# Detection.net
KiCad netlist of a schematic drawn in Altium Designer
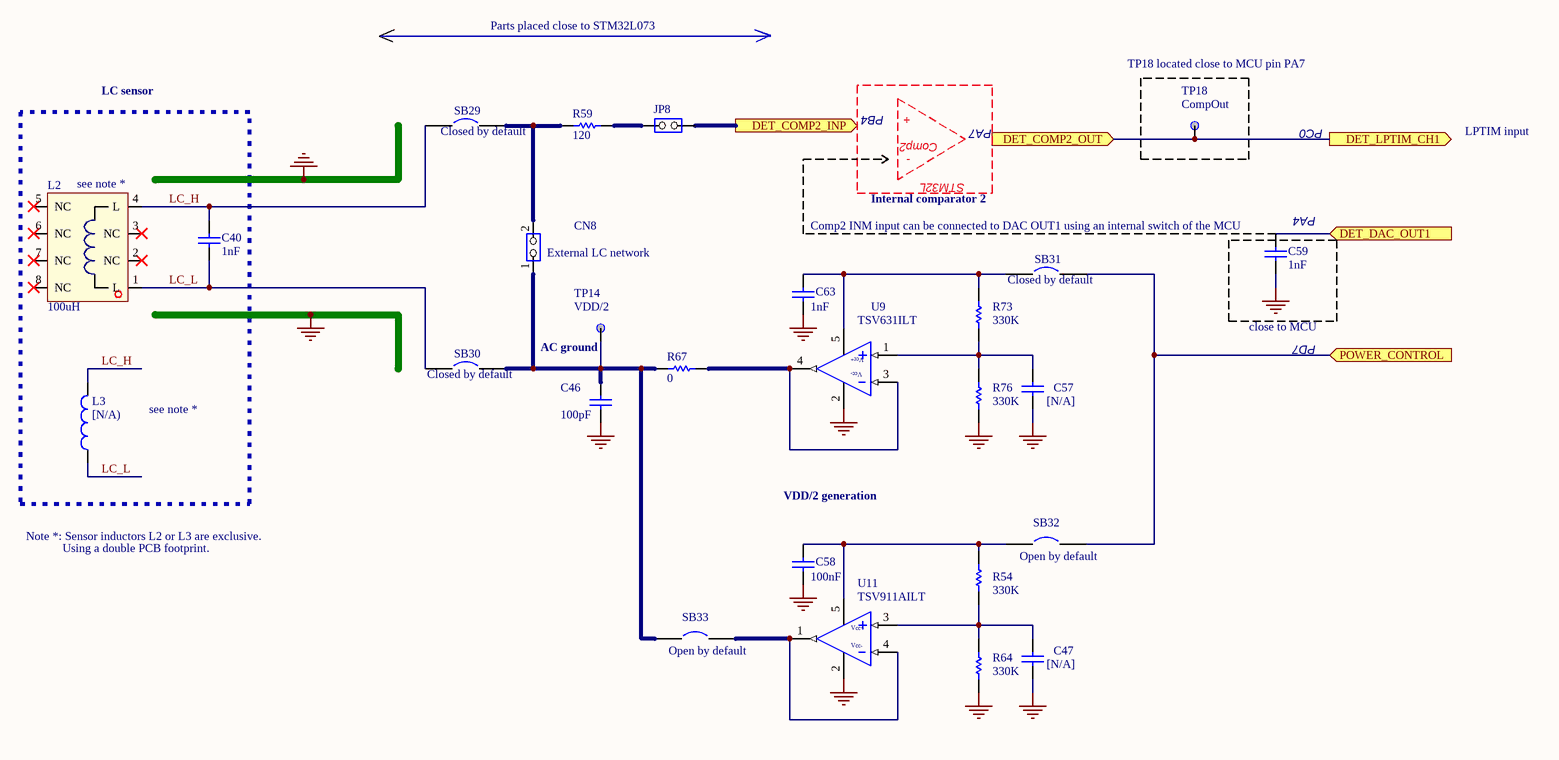
[diagram p0: Detection.SchDoc]

(export (version "E")
  (design (tool "Eeschema 10.0.6"))
  (components
    (comp (ref "C40")
      (value "1nF")
      (footprint "0603C")
      (description "Capacitor")
      (libsource (lib "MCD_TOOLS") (part "Capacitor_ST"))
    )
    (comp (ref "C46")
      (value "100pF")
      (footprint "0402C")
      (description "Capacitor")
      (libsource (lib "MCD_TOOLS") (part "Capacitor_ST"))
    )
    (comp (ref "C47")
      (value "[N/A]")
      (footprint "0603C")
      (description "Capacitor")
      (libsource (lib "MCD_TOOLS") (part "Capacitor_ST"))
    )
    (comp (ref "C57")
      (value "[N/A]")
      (footprint "0603C")
      (description "Capacitor")
      (libsource (lib "MCD_TOOLS") (part "Capacitor_ST"))
    )
    (comp (ref "C58")
      (value "100nF")
      (footprint "0402C")
      (description "Capacitor")
      (libsource (lib "MCD_TOOLS") (part "Capacitor_ST"))
    )
    (comp (ref "C59")
      (value "1nF")
      (footprint "0603C")
      (description "Capacitor")
      (libsource (lib "MCD_TOOLS") (part "Capacitor_ST"))
    )
    (comp (ref "C63")
      (value "1nF")
      (footprint "0402C")
      (description "Capacitor")
      (libsource (lib "MCD_TOOLS") (part "Capacitor_ST"))
    )
    (comp (ref "CN8")
      (value "Header 2X1")
      (footprint "SIP2")
      (fields (field (name "SILKSCREEN") "External LC network"))
      (libsource (lib "") (part "JP2_1"))
    )
    (comp (ref "JP8") (value "~") (footprint "SIP2") (libsource (lib "*") (part "JP2")))
    (comp (ref "L2")
      (value "100uH")
      (footprint "ER95")
      (description "Wurth E core inductor 750315110")
      (libsource (lib "Almos") (part "Wurth_ER9.5"))
    )
    (comp (ref "L3")
      (value "[N/A)")
      (footprint "LSM2_4R4X3R2_H3")
      (description "Cyntec/Delta  Inductor SIE4734-101")
      (fields (field (name "PUBLISHER") "Altium Limited"))
      (libsource (lib "Miscellaneous Devices") (part "Inductor"))
    )
    (comp (ref "R54")
      (value "330K")
      (footprint "0402R")
      (description "Resistor")
      (fields (field (name "PUBLISHER") "Altium Limited"))
      (libsource (lib "Miscellaneous Devices") (part "Res1"))
    )
    (comp (ref "R59")
      (value "120")
      (footprint "0603R")
      (description "Resistor")
      (fields (field (name "PUBLISHER") "Altium Limited"))
      (libsource (lib "Miscellaneous Devices") (part "Res1"))
    )
    (comp (ref "R64")
      (value "330K")
      (footprint "0402R")
      (description "Resistor")
      (fields (field (name "PUBLISHER") "Altium Limited"))
      (libsource (lib "Miscellaneous Devices") (part "Res1"))
    )
    (comp (ref "R67")
      (value "0")
      (footprint "0603R")
      (description "Resistor")
      (fields (field (name "PUBLISHER") "Altium Limited"))
      (libsource (lib "Miscellaneous Devices") (part "Res1"))
    )
    (comp (ref "R73")
      (value "330K")
      (footprint "0402R")
      (description "Resistor")
      (fields (field (name "PUBLISHER") "Altium Limited"))
      (libsource (lib "Miscellaneous Devices") (part "Res1"))
    )
    (comp (ref "R76")
      (value "330K")
      (footprint "0402R")
      (description "Resistor")
      (fields (field (name "PUBLISHER") "Altium Limited"))
      (libsource (lib "Miscellaneous Devices") (part "Res1"))
    )
    (comp (ref "SB29")
      (value "Closed by default")
      (footprint "SB_0603")
      (description "Circuit Breaker")
      (fields (field (name "PUBLISHER") "Altium Limited"))
      (libsource (lib "Miscellaneous Devices") (part "Circuit Breaker"))
    )
    (comp (ref "SB30")
      (value "Closed by default")
      (footprint "SB_0603")
      (description "Circuit Breaker")
      (fields (field (name "PUBLISHER") "Altium Limited"))
      (libsource (lib "Miscellaneous Devices") (part "Circuit Breaker"))
    )
    (comp (ref "SB31")
      (value "Closed by default")
      (footprint "SB_0603")
      (description "Circuit Breaker")
      (fields (field (name "PUBLISHER") "Altium Limited"))
      (libsource (lib "Miscellaneous Devices") (part "Circuit Breaker"))
    )
    (comp (ref "SB32")
      (value "Open by default")
      (footprint "SB_0603")
      (description "Circuit Breaker")
      (fields (field (name "PUBLISHER") "Altium Limited"))
      (libsource (lib "Miscellaneous Devices") (part "Circuit Breaker"))
    )
    (comp (ref "SB33")
      (value "Open by default")
      (footprint "SB_0603")
      (description "Circuit Breaker")
      (fields (field (name "PUBLISHER") "Altium Limited"))
      (libsource (lib "Miscellaneous Devices") (part "Circuit Breaker"))
    )
    (comp (ref "TP14")
      (value "TP")
      (footprint "TP")
      (fields (field (name "SILKSCREEN") "VDD/2"))
      (libsource (lib "*") (part "TP"))
    )
    (comp (ref "TP18")
      (value "TP")
      (footprint "TP")
      (fields (field (name "SILKSCREEN") "CompOut"))
      (libsource (lib "*") (part "TP"))
    )
    (comp (ref "U9")
      (value "TSV631ILT")
      (footprint "SOT-23-5L")
      (description "single OpAmp 60 µA, 880 kHz, 5 V CMOS")
      (libsource (lib "Almos") (part "TSV631ILT"))
    )
    (comp (ref "U11")
      (value "TSV911AILT")
      (footprint "SOT-23-5L")
      (description "single 8MHz  operational amplifiers")
      (libsource (lib "Almos") (part "TSV911ILT"))
    )
  )
  (nets
    (net (code "1") (name "/DET_COMP2_INP") (class "Default")
      (node (ref "JP8") (pin "2") (pinfunction "NO_2") (pintype "passive"))
    )
    (net (code "2") (name "/DET_COMP2_OUT") (class "Default")
      (node (ref "TP18") (pin "1") (pinfunction "1_1") (pintype "passive"))
    )
    (net (code "3") (name "/DET_DAC_OUT1") (class "Default")
      (node (ref "C59") (pin "1") (pinfunction "1_1") (pintype "passive"))
    )
    (net (code "4") (name "/LC_H") (class "Default")
      (node (ref "C40") (pin "2") (pinfunction "2_2") (pintype "passive"))
      (node (ref "L2") (pin "4") (pinfunction "L_4") (pintype "passive"))
      (node (ref "L3") (pin "2") (pinfunction "2_2") (pintype "passive"))
      (node (ref "SB29") (pin "1") (pinfunction "1_1") (pintype "passive"))
    )
    (net (code "5") (name "/LC_L") (class "Default")
      (node (ref "C40") (pin "1") (pinfunction "1_1") (pintype "passive"))
      (node (ref "L2") (pin "1") (pinfunction "L_1") (pintype "passive"))
      (node (ref "L3") (pin "1") (pinfunction "1_1") (pintype "passive"))
      (node (ref "SB30") (pin "1") (pinfunction "1_1") (pintype "passive"))
    )
    (net (code "6") (name "/POWER_CONTROL") (class "Default")
      (node (ref "SB31") (pin "2") (pinfunction "2_2") (pintype "passive"))
      (node (ref "SB32") (pin "2") (pinfunction "2_2") (pintype "passive"))
    )
    (net (code "7") (name "GND") (class "Default")
      (node (ref "C46") (pin "1") (pinfunction "1_1") (pintype "passive"))
      (node (ref "C47") (pin "2") (pinfunction "2_2") (pintype "passive"))
      (node (ref "C57") (pin "2") (pinfunction "2_2") (pintype "passive"))
      (node (ref "C58") (pin "2") (pinfunction "2_2") (pintype "passive"))
      (node (ref "C59") (pin "2") (pinfunction "2_2") (pintype "passive"))
      (node (ref "C63") (pin "2") (pinfunction "2_2") (pintype "passive"))
      (node (ref "R64") (pin "2") (pinfunction "2_2") (pintype "passive"))
      (node (ref "R76") (pin "2") (pinfunction "2_2") (pintype "passive"))
      (node (ref "U11") (pin "2") (pinfunction "Vcc-_2") (pintype "power_in"))
      (node (ref "U9") (pin "2") (pinfunction "Vcc-_2") (pintype "power_in"))
    )
    (net (code "8") (name "Net-(CN8-COMMON)") (class "Default")
      (node (ref "C46") (pin "2") (pinfunction "2_2") (pintype "passive"))
      (node (ref "CN8") (pin "1") (pinfunction "COMMON_1") (pintype "passive"))
      (node (ref "R67") (pin "1") (pinfunction "1_1") (pintype "passive"))
      (node (ref "SB30") (pin "2") (pinfunction "2_2") (pintype "passive"))
      (node (ref "SB33") (pin "1") (pinfunction "1_1") (pintype "passive"))
      (node (ref "TP14") (pin "1") (pinfunction "1_1") (pintype "passive"))
    )
    (net (code "9") (name "Net-(CN8-NO)") (class "Default")
      (node (ref "CN8") (pin "2") (pinfunction "NO_2") (pintype "passive"))
      (node (ref "R59") (pin "1") (pinfunction "1_1") (pintype "passive"))
      (node (ref "SB29") (pin "2") (pinfunction "2_2") (pintype "passive"))
    )
    (net (code "10") (name "Net-(JP8-COMMON)") (class "Default")
      (node (ref "JP8") (pin "1") (pinfunction "COMMON_1") (pintype "passive"))
      (node (ref "R59") (pin "2") (pinfunction "2_2") (pintype "passive"))
    )
    (net (code "11") (name "Net-(U9-OUT)") (class "Default")
      (node (ref "R67") (pin "2") (pinfunction "2_2") (pintype "passive"))
      (node (ref "U9") (pin "3") (pinfunction "Vm_3") (pintype "input"))
      (node (ref "U9") (pin "4") (pinfunction "OUT_4") (pintype "output"))
    )
    (net (code "12") (name "Net-(U9-Vcc+)") (class "Default")
      (node (ref "C63") (pin "1") (pinfunction "1_1") (pintype "passive"))
      (node (ref "R73") (pin "1") (pinfunction "1_1") (pintype "passive"))
      (node (ref "SB31") (pin "1") (pinfunction "1_1") (pintype "passive"))
      (node (ref "U9") (pin "5") (pinfunction "Vcc+_5") (pintype "power_in"))
    )
    (net (code "13") (name "Net-(U9-Vp)") (class "Default")
      (node (ref "C57") (pin "1") (pinfunction "1_1") (pintype "passive"))
      (node (ref "R73") (pin "2") (pinfunction "2_2") (pintype "passive"))
      (node (ref "R76") (pin "1") (pinfunction "1_1") (pintype "passive"))
      (node (ref "U9") (pin "1") (pinfunction "Vp_1") (pintype "input"))
    )
    (net (code "14") (name "Net-(U11-OUT)") (class "Default")
      (node (ref "SB33") (pin "2") (pinfunction "2_2") (pintype "passive"))
      (node (ref "U11") (pin "1") (pinfunction "OUT_1") (pintype "output"))
      (node (ref "U11") (pin "4") (pinfunction "Vm_4") (pintype "input"))
    )
    (net (code "15") (name "Net-(U11-Vcc+)") (class "Default")
      (node (ref "C58") (pin "1") (pinfunction "1_1") (pintype "passive"))
      (node (ref "R54") (pin "1") (pinfunction "1_1") (pintype "passive"))
      (node (ref "SB32") (pin "1") (pinfunction "1_1") (pintype "passive"))
      (node (ref "U11") (pin "5") (pinfunction "Vcc+_5") (pintype "power_in"))
    )
    (net (code "16") (name "Net-(U11-Vp)") (class "Default")
      (node (ref "C47") (pin "1") (pinfunction "1_1") (pintype "passive"))
      (node (ref "R54") (pin "2") (pinfunction "2_2") (pintype "passive"))
      (node (ref "R64") (pin "1") (pinfunction "1_1") (pintype "passive"))
      (node (ref "U11") (pin "3") (pinfunction "Vp_3") (pintype "input"))
    )
    (net (code "17") (name "unconnected-(L2-NC-Pad2)") (class "Default")
      (node (ref "L2") (pin "2") (pinfunction "NC_2") (pintype "passive+no_connect"))
    )
    (net (code "18") (name "unconnected-(L2-NC-Pad3)") (class "Default")
      (node (ref "L2") (pin "3") (pinfunction "NC_3") (pintype "passive+no_connect"))
    )
    (net (code "19") (name "unconnected-(L2-NC-Pad5)") (class "Default")
      (node (ref "L2") (pin "5") (pinfunction "NC_5") (pintype "passive+no_connect"))
    )
    (net (code "20") (name "unconnected-(L2-NC-Pad6)") (class "Default")
      (node (ref "L2") (pin "6") (pinfunction "NC_6") (pintype "passive+no_connect"))
    )
    (net (code "21") (name "unconnected-(L2-NC-Pad7)") (class "Default")
      (node (ref "L2") (pin "7") (pinfunction "NC_7") (pintype "passive+no_connect"))
    )
    (net (code "22") (name "unconnected-(L2-NC-Pad8)") (class "Default")
      (node (ref "L2") (pin "8") (pinfunction "NC_8") (pintype "passive+no_connect"))
    )
  )
)
